# HydrophoneGroup1FilterAndAmpCircuit.net
KiCad netlist of a schematic drawn in Altium Designer
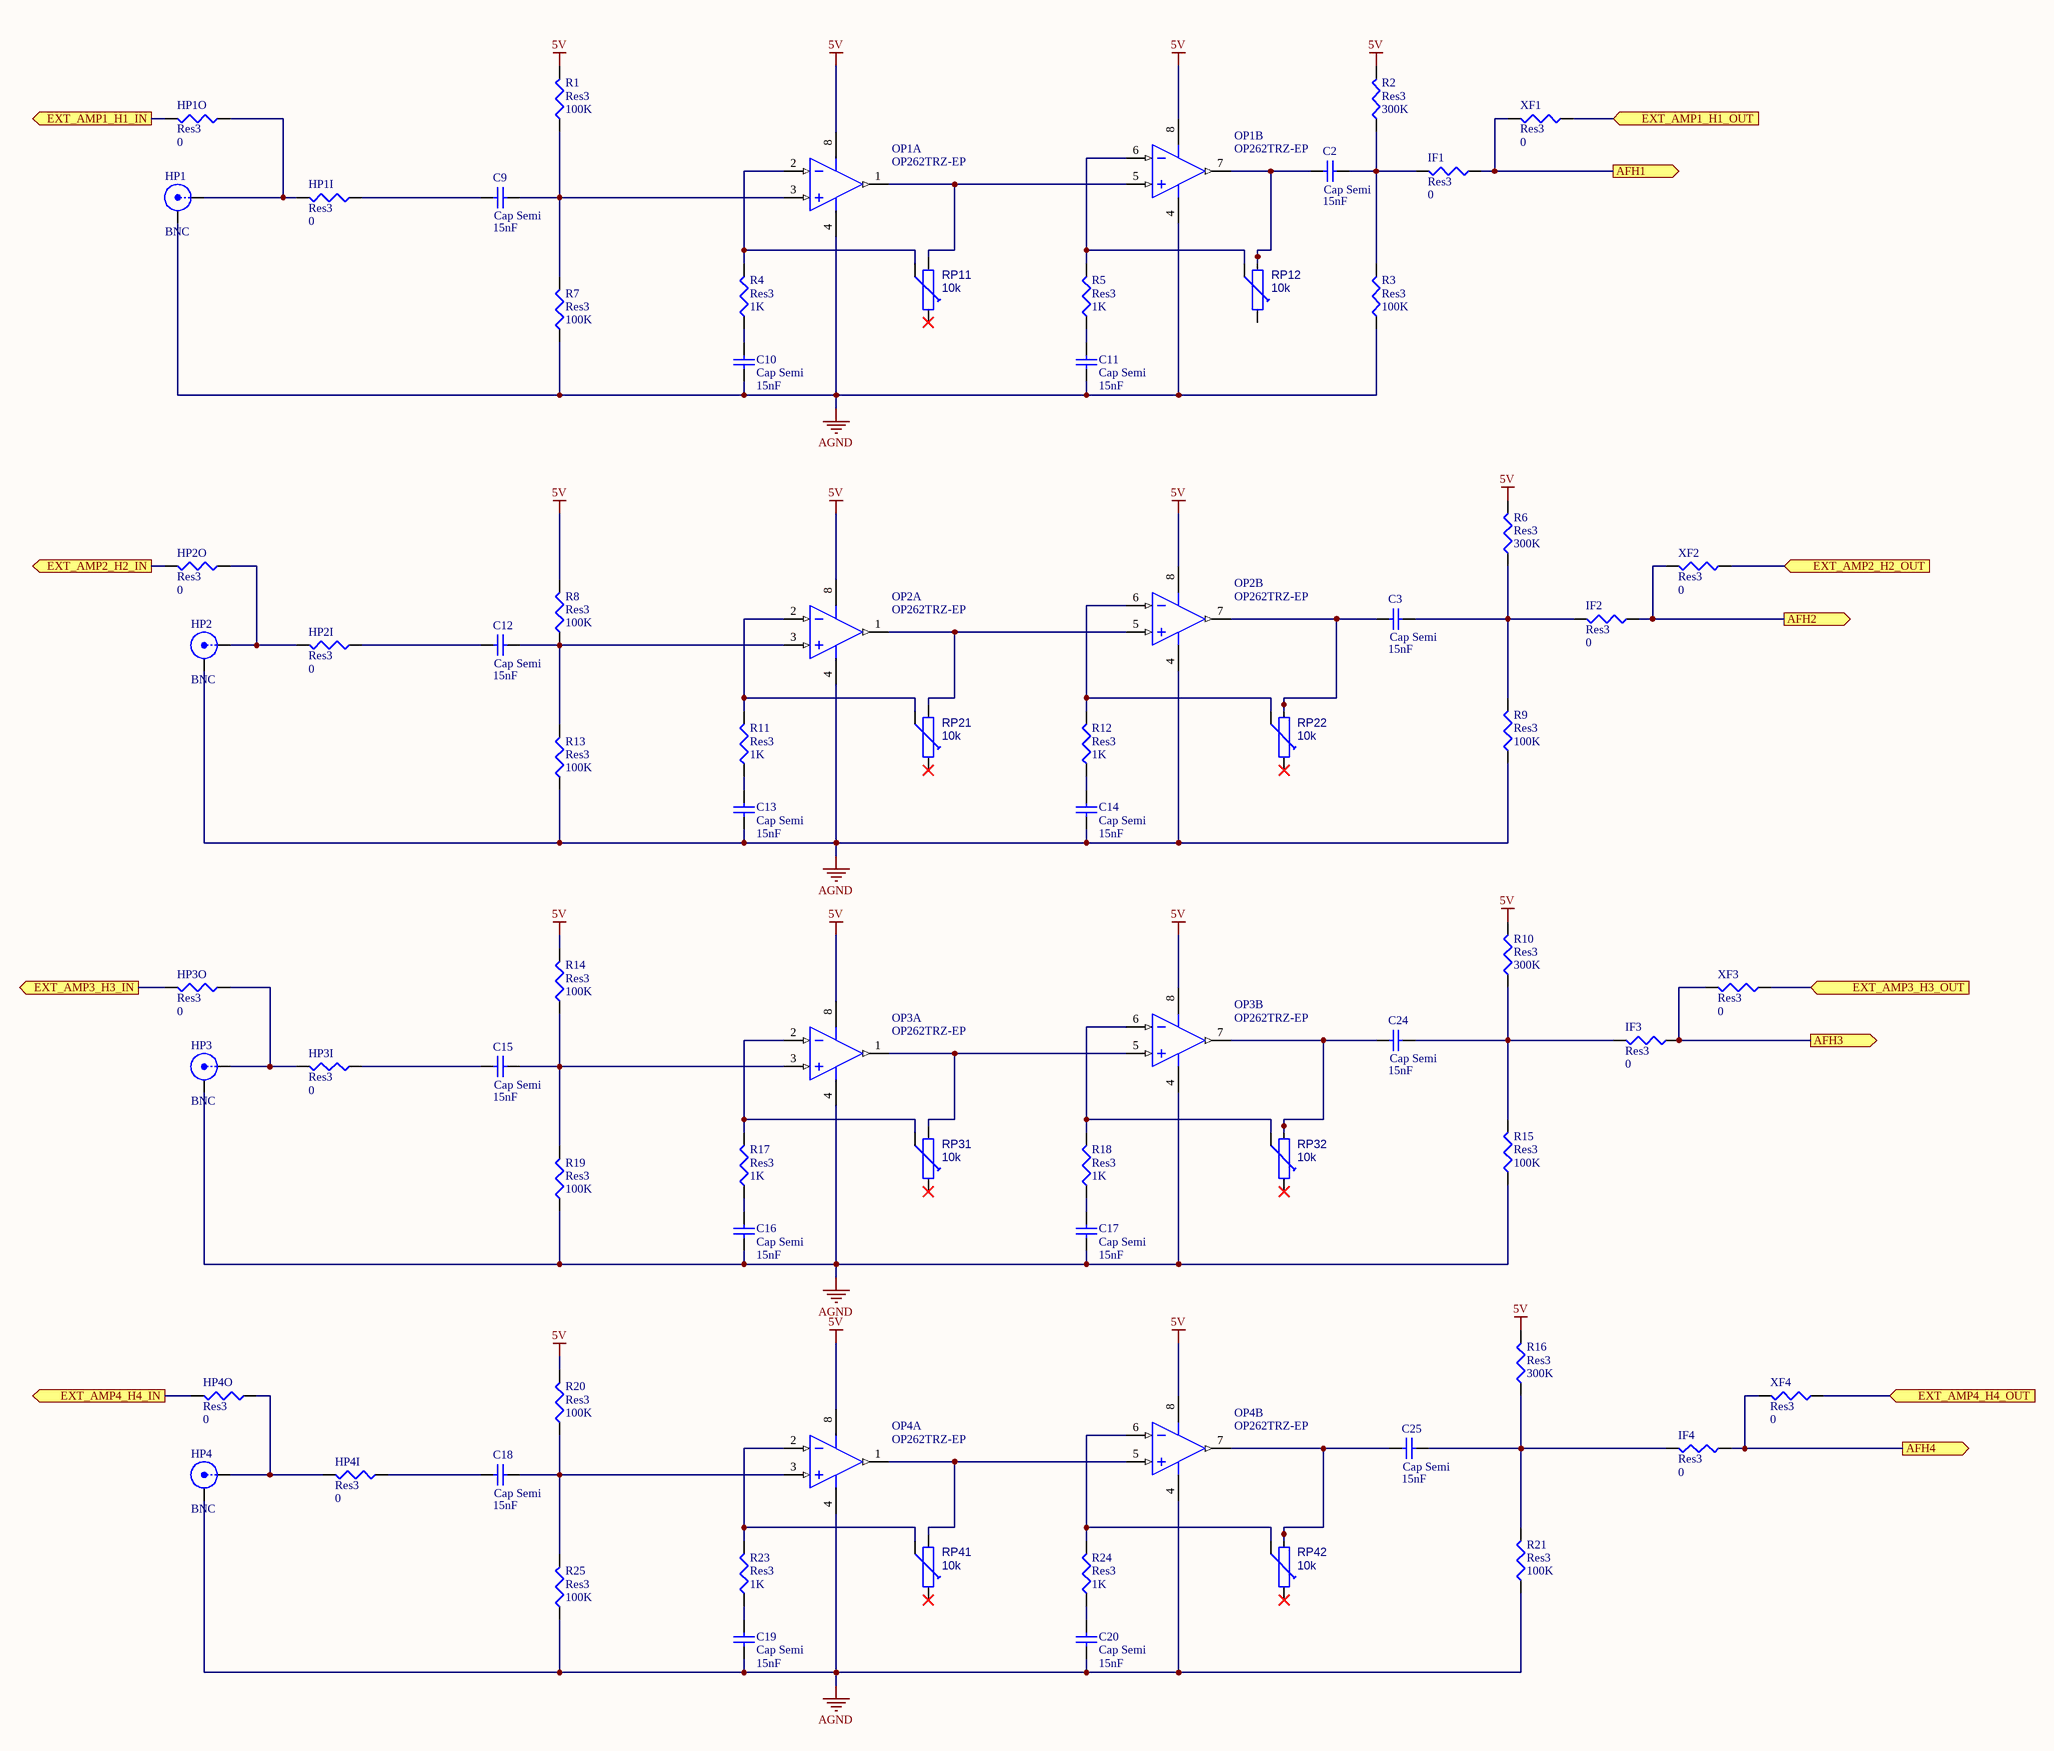
[diagram p0: HydrophoneGroup1FilterAndAmpCircuit.SchDoc]

(export (version "E")
  (design (tool "Eeschema 10.0.6"))
  (components
    (comp (ref "C2")
      (value "Cap Semi")
      (footprint "C0805")
      (description "Capacitor (Semiconductor SIM Model)")
      (fields (field (name "ALTIUM_VALUE") "15nF") (field (name "PUBLISHER") "Altium Limited"))
      (libsource (lib "Miscellaneous Devices") (part "Cap Semi"))
    )
    (comp (ref "C3")
      (value "Cap Semi")
      (footprint "C0805")
      (description "Capacitor (Semiconductor SIM Model)")
      (fields (field (name "ALTIUM_VALUE") "15nF") (field (name "PUBLISHER") "Altium Limited"))
      (libsource (lib "Miscellaneous Devices") (part "Cap Semi"))
    )
    (comp (ref "C9")
      (value "Cap Semi")
      (footprint "C0805")
      (description "Capacitor (Semiconductor SIM Model)")
      (fields (field (name "ALTIUM_VALUE") "15nF") (field (name "PUBLISHER") "Altium Limited"))
      (libsource (lib "Miscellaneous Devices") (part "Cap Semi"))
    )
    (comp (ref "C10")
      (value "Cap Semi")
      (footprint "C0805")
      (description "Capacitor (Semiconductor SIM Model)")
      (fields (field (name "ALTIUM_VALUE") "15nF") (field (name "PUBLISHER") "Altium Limited"))
      (libsource (lib "Miscellaneous Devices") (part "Cap Semi"))
    )
    (comp (ref "C11")
      (value "Cap Semi")
      (footprint "C0805")
      (description "Capacitor (Semiconductor SIM Model)")
      (fields (field (name "ALTIUM_VALUE") "15nF") (field (name "PUBLISHER") "Altium Limited"))
      (libsource (lib "Miscellaneous Devices") (part "Cap Semi"))
    )
    (comp (ref "C12")
      (value "Cap Semi")
      (footprint "C0805")
      (description "Capacitor (Semiconductor SIM Model)")
      (fields (field (name "ALTIUM_VALUE") "15nF") (field (name "PUBLISHER") "Altium Limited"))
      (libsource (lib "Miscellaneous Devices") (part "Cap Semi"))
    )
    (comp (ref "C13")
      (value "Cap Semi")
      (footprint "C0805")
      (description "Capacitor (Semiconductor SIM Model)")
      (fields (field (name "ALTIUM_VALUE") "15nF") (field (name "PUBLISHER") "Altium Limited"))
      (libsource (lib "Miscellaneous Devices") (part "Cap Semi"))
    )
    (comp (ref "C14")
      (value "Cap Semi")
      (footprint "C0805")
      (description "Capacitor (Semiconductor SIM Model)")
      (fields (field (name "ALTIUM_VALUE") "15nF") (field (name "PUBLISHER") "Altium Limited"))
      (libsource (lib "Miscellaneous Devices") (part "Cap Semi"))
    )
    (comp (ref "C15")
      (value "Cap Semi")
      (footprint "C0805")
      (description "Capacitor (Semiconductor SIM Model)")
      (fields (field (name "ALTIUM_VALUE") "15nF") (field (name "PUBLISHER") "Altium Limited"))
      (libsource (lib "Miscellaneous Devices") (part "Cap Semi"))
    )
    (comp (ref "C16")
      (value "Cap Semi")
      (footprint "C0805")
      (description "Capacitor (Semiconductor SIM Model)")
      (fields (field (name "ALTIUM_VALUE") "15nF") (field (name "PUBLISHER") "Altium Limited"))
      (libsource (lib "Miscellaneous Devices") (part "Cap Semi"))
    )
    (comp (ref "C17")
      (value "Cap Semi")
      (footprint "C0805")
      (description "Capacitor (Semiconductor SIM Model)")
      (fields (field (name "ALTIUM_VALUE") "15nF") (field (name "PUBLISHER") "Altium Limited"))
      (libsource (lib "Miscellaneous Devices") (part "Cap Semi"))
    )
    (comp (ref "C18")
      (value "Cap Semi")
      (footprint "C0805")
      (description "Capacitor (Semiconductor SIM Model)")
      (fields (field (name "ALTIUM_VALUE") "15nF") (field (name "PUBLISHER") "Altium Limited"))
      (libsource (lib "Miscellaneous Devices") (part "Cap Semi"))
    )
    (comp (ref "C19")
      (value "Cap Semi")
      (footprint "C0805")
      (description "Capacitor (Semiconductor SIM Model)")
      (fields (field (name "ALTIUM_VALUE") "15nF") (field (name "PUBLISHER") "Altium Limited"))
      (libsource (lib "Miscellaneous Devices") (part "Cap Semi"))
    )
    (comp (ref "C20")
      (value "Cap Semi")
      (footprint "C0805")
      (description "Capacitor (Semiconductor SIM Model)")
      (fields (field (name "ALTIUM_VALUE") "15nF") (field (name "PUBLISHER") "Altium Limited"))
      (libsource (lib "Miscellaneous Devices") (part "Cap Semi"))
    )
    (comp (ref "C24")
      (value "Cap Semi")
      (footprint "C0805")
      (description "Capacitor (Semiconductor SIM Model)")
      (fields (field (name "ALTIUM_VALUE") "15nF") (field (name "PUBLISHER") "Altium Limited"))
      (libsource (lib "Miscellaneous Devices") (part "Cap Semi"))
    )
    (comp (ref "C25")
      (value "Cap Semi")
      (footprint "C0805")
      (description "Capacitor (Semiconductor SIM Model)")
      (fields (field (name "ALTIUM_VALUE") "15nF") (field (name "PUBLISHER") "Altium Limited"))
      (libsource (lib "Miscellaneous Devices") (part "Cap Semi"))
    )
    (comp (ref "HP1")
      (value "BNC")
      (footprint "BNC_RA CON")
      (description "BNC Elbow Connector")
      (fields (field (name "PUBLISHER") "Altium Limited"))
      (libsource (lib "Miscellaneous Connectors") (part "BNC"))
    )
    (comp (ref "HP1I")
      (value "Res3")
      (footprint "J1-0603")
      (description "Resistor")
      (fields (field (name "ALTIUM_VALUE") "0") (field (name "PUBLISHER") "Altium Limited"))
      (libsource (lib "Miscellaneous Devices") (part "Res3"))
    )
    (comp (ref "HP1O")
      (value "Res3")
      (footprint "J1-0603")
      (description "Resistor")
      (fields (field (name "ALTIUM_VALUE") "0") (field (name "PUBLISHER") "Altium Limited"))
      (libsource (lib "Miscellaneous Devices") (part "Res3"))
    )
    (comp (ref "HP2")
      (value "BNC")
      (footprint "BNC_RA CON")
      (description "BNC Elbow Connector")
      (fields (field (name "PUBLISHER") "Altium Limited"))
      (libsource (lib "Miscellaneous Connectors") (part "BNC"))
    )
    (comp (ref "HP2I")
      (value "Res3")
      (footprint "J1-0603")
      (description "Resistor")
      (fields (field (name "ALTIUM_VALUE") "0") (field (name "PUBLISHER") "Altium Limited"))
      (libsource (lib "Miscellaneous Devices") (part "Res3"))
    )
    (comp (ref "HP2O")
      (value "Res3")
      (footprint "J1-0603")
      (description "Resistor")
      (fields (field (name "ALTIUM_VALUE") "0") (field (name "PUBLISHER") "Altium Limited"))
      (libsource (lib "Miscellaneous Devices") (part "Res3"))
    )
    (comp (ref "HP3")
      (value "BNC")
      (footprint "BNC_RA CON")
      (description "BNC Elbow Connector")
      (fields (field (name "PUBLISHER") "Altium Limited"))
      (libsource (lib "Miscellaneous Connectors") (part "BNC"))
    )
    (comp (ref "HP3I")
      (value "Res3")
      (footprint "J1-0603")
      (description "Resistor")
      (fields (field (name "ALTIUM_VALUE") "0") (field (name "PUBLISHER") "Altium Limited"))
      (libsource (lib "Miscellaneous Devices") (part "Res3"))
    )
    (comp (ref "HP3O")
      (value "Res3")
      (footprint "J1-0603")
      (description "Resistor")
      (fields (field (name "ALTIUM_VALUE") "0") (field (name "PUBLISHER") "Altium Limited"))
      (libsource (lib "Miscellaneous Devices") (part "Res3"))
    )
    (comp (ref "HP4")
      (value "BNC")
      (footprint "BNC_RA CON")
      (description "BNC Elbow Connector")
      (fields (field (name "PUBLISHER") "Altium Limited"))
      (libsource (lib "Miscellaneous Connectors") (part "BNC"))
    )
    (comp (ref "HP4I")
      (value "Res3")
      (footprint "J1-0603")
      (description "Resistor")
      (fields (field (name "ALTIUM_VALUE") "0") (field (name "PUBLISHER") "Altium Limited"))
      (libsource (lib "Miscellaneous Devices") (part "Res3"))
    )
    (comp (ref "HP4O")
      (value "Res3")
      (footprint "J1-0603")
      (description "Resistor")
      (fields (field (name "ALTIUM_VALUE") "0") (field (name "PUBLISHER") "Altium Limited"))
      (libsource (lib "Miscellaneous Devices") (part "Res3"))
    )
    (comp (ref "IF1")
      (value "Res3")
      (footprint "J1-0603")
      (description "Resistor")
      (fields (field (name "ALTIUM_VALUE") "0") (field (name "PUBLISHER") "Altium Limited"))
      (libsource (lib "Miscellaneous Devices") (part "Res3"))
    )
    (comp (ref "IF2")
      (value "Res3")
      (footprint "J1-0603")
      (description "Resistor")
      (fields (field (name "ALTIUM_VALUE") "0") (field (name "PUBLISHER") "Altium Limited"))
      (libsource (lib "Miscellaneous Devices") (part "Res3"))
    )
    (comp (ref "IF3")
      (value "Res3")
      (footprint "J1-0603")
      (description "Resistor")
      (fields (field (name "ALTIUM_VALUE") "0") (field (name "PUBLISHER") "Altium Limited"))
      (libsource (lib "Miscellaneous Devices") (part "Res3"))
    )
    (comp (ref "IF4")
      (value "Res3")
      (footprint "J1-0603")
      (description "Resistor")
      (fields (field (name "ALTIUM_VALUE") "0") (field (name "PUBLISHER") "Altium Limited"))
      (libsource (lib "Miscellaneous Devices") (part "Res3"))
    )
    (comp (ref "OP1")
      (value "OP262TRZ-EP")
      (footprint "ADI-R-8_N")
      (fields (field (name "GENERIC PART NUMBER") "OP262") (field (name "MANUFACTURER") "Analog Devices"))
      (libsource (lib "Analog Devices Operational Amplifiers") (part "OP262TRZ-EP"))
    )
    (comp (ref "OP2")
      (value "OP262TRZ-EP")
      (footprint "ADI-R-8_N")
      (fields (field (name "GENERIC PART NUMBER") "OP262") (field (name "MANUFACTURER") "Analog Devices"))
      (libsource (lib "Analog Devices Operational Amplifiers") (part "OP262TRZ-EP"))
    )
    (comp (ref "OP3")
      (value "OP262TRZ-EP")
      (footprint "ADI-R-8_N")
      (fields (field (name "GENERIC PART NUMBER") "OP262") (field (name "MANUFACTURER") "Analog Devices"))
      (libsource (lib "Analog Devices Operational Amplifiers") (part "OP262TRZ-EP"))
    )
    (comp (ref "OP4")
      (value "OP262TRZ-EP")
      (footprint "ADI-R-8_N")
      (fields (field (name "GENERIC PART NUMBER") "OP262") (field (name "MANUFACTURER") "Analog Devices"))
      (libsource (lib "Analog Devices Operational Amplifiers") (part "OP262TRZ-EP"))
    )
    (comp (ref "R1")
      (value "Res3")
      (footprint "J1-0603")
      (description "Resistor")
      (fields (field (name "ALTIUM_VALUE") "100K") (field (name "PUBLISHER") "Altium Limited"))
      (libsource (lib "Miscellaneous Devices") (part "Res3"))
    )
    (comp (ref "R2")
      (value "Res3")
      (footprint "J1-0603")
      (description "Resistor")
      (fields (field (name "ALTIUM_VALUE") "300K") (field (name "PUBLISHER") "Altium Limited"))
      (libsource (lib "Miscellaneous Devices") (part "Res3"))
    )
    (comp (ref "R3")
      (value "Res3")
      (footprint "J1-0603")
      (description "Resistor")
      (fields (field (name "ALTIUM_VALUE") "100K") (field (name "PUBLISHER") "Altium Limited"))
      (libsource (lib "Miscellaneous Devices") (part "Res3"))
    )
    (comp (ref "R4")
      (value "Res3")
      (footprint "J1-0603")
      (description "Resistor")
      (fields (field (name "ALTIUM_VALUE") "1K") (field (name "PUBLISHER") "Altium Limited"))
      (libsource (lib "Miscellaneous Devices") (part "Res3"))
    )
    (comp (ref "R5")
      (value "Res3")
      (footprint "J1-0603")
      (description "Resistor")
      (fields (field (name "ALTIUM_VALUE") "1K") (field (name "PUBLISHER") "Altium Limited"))
      (libsource (lib "Miscellaneous Devices") (part "Res3"))
    )
    (comp (ref "R6")
      (value "Res3")
      (footprint "J1-0603")
      (description "Resistor")
      (fields (field (name "ALTIUM_VALUE") "300K") (field (name "PUBLISHER") "Altium Limited"))
      (libsource (lib "Miscellaneous Devices") (part "Res3"))
    )
    (comp (ref "R7")
      (value "Res3")
      (footprint "J1-0603")
      (description "Resistor")
      (fields (field (name "ALTIUM_VALUE") "100K") (field (name "PUBLISHER") "Altium Limited"))
      (libsource (lib "Miscellaneous Devices") (part "Res3"))
    )
    (comp (ref "R8")
      (value "Res3")
      (footprint "J1-0603")
      (description "Resistor")
      (fields (field (name "ALTIUM_VALUE") "100K") (field (name "PUBLISHER") "Altium Limited"))
      (libsource (lib "Miscellaneous Devices") (part "Res3"))
    )
    (comp (ref "R9")
      (value "Res3")
      (footprint "J1-0603")
      (description "Resistor")
      (fields (field (name "ALTIUM_VALUE") "100K") (field (name "PUBLISHER") "Altium Limited"))
      (libsource (lib "Miscellaneous Devices") (part "Res3"))
    )
    (comp (ref "R10")
      (value "Res3")
      (footprint "J1-0603")
      (description "Resistor")
      (fields (field (name "ALTIUM_VALUE") "300K") (field (name "PUBLISHER") "Altium Limited"))
      (libsource (lib "Miscellaneous Devices") (part "Res3"))
    )
    (comp (ref "R11")
      (value "Res3")
      (footprint "J1-0603")
      (description "Resistor")
      (fields (field (name "ALTIUM_VALUE") "1K") (field (name "PUBLISHER") "Altium Limited"))
      (libsource (lib "Miscellaneous Devices") (part "Res3"))
    )
    (comp (ref "R12")
      (value "Res3")
      (footprint "J1-0603")
      (description "Resistor")
      (fields (field (name "ALTIUM_VALUE") "1K") (field (name "PUBLISHER") "Altium Limited"))
      (libsource (lib "Miscellaneous Devices") (part "Res3"))
    )
    (comp (ref "R13")
      (value "Res3")
      (footprint "J1-0603")
      (description "Resistor")
      (fields (field (name "ALTIUM_VALUE") "100K") (field (name "PUBLISHER") "Altium Limited"))
      (libsource (lib "Miscellaneous Devices") (part "Res3"))
    )
    (comp (ref "R14")
      (value "Res3")
      (footprint "J1-0603")
      (description "Resistor")
      (fields (field (name "ALTIUM_VALUE") "100K") (field (name "PUBLISHER") "Altium Limited"))
      (libsource (lib "Miscellaneous Devices") (part "Res3"))
    )
    (comp (ref "R15")
      (value "Res3")
      (footprint "J1-0603")
      (description "Resistor")
      (fields (field (name "ALTIUM_VALUE") "100K") (field (name "PUBLISHER") "Altium Limited"))
      (libsource (lib "Miscellaneous Devices") (part "Res3"))
    )
    (comp (ref "R16")
      (value "Res3")
      (footprint "J1-0603")
      (description "Resistor")
      (fields (field (name "ALTIUM_VALUE") "300K") (field (name "PUBLISHER") "Altium Limited"))
      (libsource (lib "Miscellaneous Devices") (part "Res3"))
    )
    (comp (ref "R17")
      (value "Res3")
      (footprint "J1-0603")
      (description "Resistor")
      (fields (field (name "ALTIUM_VALUE") "1K") (field (name "PUBLISHER") "Altium Limited"))
      (libsource (lib "Miscellaneous Devices") (part "Res3"))
    )
    (comp (ref "R18")
      (value "Res3")
      (footprint "J1-0603")
      (description "Resistor")
      (fields (field (name "ALTIUM_VALUE") "1K") (field (name "PUBLISHER") "Altium Limited"))
      (libsource (lib "Miscellaneous Devices") (part "Res3"))
    )
    (comp (ref "R19")
      (value "Res3")
      (footprint "J1-0603")
      (description "Resistor")
      (fields (field (name "ALTIUM_VALUE") "100K") (field (name "PUBLISHER") "Altium Limited"))
      (libsource (lib "Miscellaneous Devices") (part "Res3"))
    )
    (comp (ref "R20")
      (value "Res3")
      (footprint "J1-0603")
      (description "Resistor")
      (fields (field (name "ALTIUM_VALUE") "100K") (field (name "PUBLISHER") "Altium Limited"))
      (libsource (lib "Miscellaneous Devices") (part "Res3"))
    )
    (comp (ref "R21")
      (value "Res3")
      (footprint "J1-0603")
      (description "Resistor")
      (fields (field (name "ALTIUM_VALUE") "100K") (field (name "PUBLISHER") "Altium Limited"))
      (libsource (lib "Miscellaneous Devices") (part "Res3"))
    )
    (comp (ref "R23")
      (value "Res3")
      (footprint "J1-0603")
      (description "Resistor")
      (fields (field (name "ALTIUM_VALUE") "1K") (field (name "PUBLISHER") "Altium Limited"))
      (libsource (lib "Miscellaneous Devices") (part "Res3"))
    )
    (comp (ref "R24")
      (value "Res3")
      (footprint "J1-0603")
      (description "Resistor")
      (fields (field (name "ALTIUM_VALUE") "1K") (field (name "PUBLISHER") "Altium Limited"))
      (libsource (lib "Miscellaneous Devices") (part "Res3"))
    )
    (comp (ref "R25")
      (value "Res3")
      (footprint "J1-0603")
      (description "Resistor")
      (fields (field (name "ALTIUM_VALUE") "100K") (field (name "PUBLISHER") "Altium Limited"))
      (libsource (lib "Miscellaneous Devices") (part "Res3"))
    )
    (comp (ref "RP11")
      (value "10k")
      (footprint "Trim_Bourns3296")
      (description "Resistor Trimmer")
      (fields
        (field (name "PART_NUMBER") "RES_Trim_Bourns3296")
        (field (name "MFR PART NUMBER") "Bourns 3296Y-1-xxxLF")
      )
      (libsource (lib "Bourns") (part "RES_Trim"))
    )
    (comp (ref "RP12")
      (value "10k")
      (footprint "Trim_Bourns3296")
      (description "Resistor Trimmer")
      (fields
        (field (name "PART_NUMBER") "RES_Trim_Bourns3296")
        (field (name "MFR PART NUMBER") "Bourns 3296Y-1-xxxLF")
      )
      (libsource (lib "Bourns") (part "RES_Trim"))
    )
    (comp (ref "RP21")
      (value "10k")
      (footprint "Trim_Bourns3296")
      (description "Resistor Trimmer")
      (fields
        (field (name "PART_NUMBER") "RES_Trim_Bourns3296")
        (field (name "MFR PART NUMBER") "Bourns 3296Y-1-xxxLF")
      )
      (libsource (lib "Bourns") (part "RES_Trim"))
    )
    (comp (ref "RP22")
      (value "10k")
      (footprint "Trim_Bourns3296")
      (description "Resistor Trimmer")
      (fields
        (field (name "PART_NUMBER") "RES_Trim_Bourns3296")
        (field (name "MFR PART NUMBER") "Bourns 3296Y-1-xxxLF")
      )
      (libsource (lib "Bourns") (part "RES_Trim"))
    )
    (comp (ref "RP31")
      (value "10k")
      (footprint "Trim_Bourns3296")
      (description "Resistor Trimmer")
      (fields
        (field (name "PART_NUMBER") "RES_Trim_Bourns3296")
        (field (name "MFR PART NUMBER") "Bourns 3296Y-1-xxxLF")
      )
      (libsource (lib "Bourns") (part "RES_Trim"))
    )
    (comp (ref "RP32")
      (value "10k")
      (footprint "Trim_Bourns3296")
      (description "Resistor Trimmer")
      (fields
        (field (name "PART_NUMBER") "RES_Trim_Bourns3296")
        (field (name "MFR PART NUMBER") "Bourns 3296Y-1-xxxLF")
      )
      (libsource (lib "Bourns") (part "RES_Trim"))
    )
    (comp (ref "RP41")
      (value "10k")
      (footprint "Trim_Bourns3296")
      (description "Resistor Trimmer")
      (fields
        (field (name "PART_NUMBER") "RES_Trim_Bourns3296")
        (field (name "MFR PART NUMBER") "Bourns 3296Y-1-xxxLF")
      )
      (libsource (lib "Bourns") (part "RES_Trim"))
    )
    (comp (ref "RP42")
      (value "10k")
      (footprint "Trim_Bourns3296")
      (description "Resistor Trimmer")
      (fields
        (field (name "PART_NUMBER") "RES_Trim_Bourns3296")
        (field (name "MFR PART NUMBER") "Bourns 3296Y-1-xxxLF")
      )
      (libsource (lib "Bourns") (part "RES_Trim"))
    )
    (comp (ref "XF1")
      (value "Res3")
      (footprint "J1-0603")
      (description "Resistor")
      (fields (field (name "ALTIUM_VALUE") "0") (field (name "PUBLISHER") "Altium Limited"))
      (libsource (lib "Miscellaneous Devices") (part "Res3"))
    )
    (comp (ref "XF2")
      (value "Res3")
      (footprint "J1-0603")
      (description "Resistor")
      (fields (field (name "ALTIUM_VALUE") "0") (field (name "PUBLISHER") "Altium Limited"))
      (libsource (lib "Miscellaneous Devices") (part "Res3"))
    )
    (comp (ref "XF3")
      (value "Res3")
      (footprint "J1-0603")
      (description "Resistor")
      (fields (field (name "ALTIUM_VALUE") "0") (field (name "PUBLISHER") "Altium Limited"))
      (libsource (lib "Miscellaneous Devices") (part "Res3"))
    )
    (comp (ref "XF4")
      (value "Res3")
      (footprint "J1-0603")
      (description "Resistor")
      (fields (field (name "ALTIUM_VALUE") "0") (field (name "PUBLISHER") "Altium Limited"))
      (libsource (lib "Miscellaneous Devices") (part "Res3"))
    )
  )
  (nets
    (net (code "1") (name "/AFH1") (class "Default")
      (node (ref "IF1") (pin "1") (pinfunction "1_1") (pintype "passive"))
      (node (ref "XF1") (pin "2") (pinfunction "2_2") (pintype "passive"))
    )
    (net (code "2") (name "/AFH2") (class "Default")
      (node (ref "IF2") (pin "1") (pinfunction "1_1") (pintype "passive"))
      (node (ref "XF2") (pin "2") (pinfunction "2_2") (pintype "passive"))
    )
    (net (code "3") (name "/AFH3") (class "Default")
      (node (ref "IF3") (pin "1") (pinfunction "1_1") (pintype "passive"))
      (node (ref "XF3") (pin "2") (pinfunction "2_2") (pintype "passive"))
    )
    (net (code "4") (name "/AFH4") (class "Default")
      (node (ref "IF4") (pin "1") (pinfunction "1_1") (pintype "passive"))
      (node (ref "XF4") (pin "2") (pinfunction "2_2") (pintype "passive"))
    )
    (net (code "5") (name "/EXT_AMP1_H1_IN") (class "Default")
      (node (ref "HP1O") (pin "2") (pinfunction "2_2") (pintype "passive"))
    )
    (net (code "6") (name "/EXT_AMP1_H1_OUT") (class "Default")
      (node (ref "XF1") (pin "1") (pinfunction "1_1") (pintype "passive"))
    )
    (net (code "7") (name "/EXT_AMP2_H2_IN") (class "Default")
      (node (ref "HP2O") (pin "2") (pinfunction "2_2") (pintype "passive"))
    )
    (net (code "8") (name "/EXT_AMP2_H2_OUT") (class "Default")
      (node (ref "XF2") (pin "1") (pinfunction "1_1") (pintype "passive"))
    )
    (net (code "9") (name "/EXT_AMP3_H3_IN") (class "Default")
      (node (ref "HP3O") (pin "2") (pinfunction "2_2") (pintype "passive"))
    )
    (net (code "10") (name "/EXT_AMP3_H3_OUT") (class "Default")
      (node (ref "XF3") (pin "1") (pinfunction "1_1") (pintype "passive"))
    )
    (net (code "11") (name "/EXT_AMP4_H4_IN") (class "Default")
      (node (ref "HP4O") (pin "2") (pinfunction "2_2") (pintype "passive"))
    )
    (net (code "12") (name "/EXT_AMP4_H4_OUT") (class "Default")
      (node (ref "XF4") (pin "1") (pinfunction "1_1") (pintype "passive"))
    )
    (net (code "13") (name "5V") (class "Default")
      (node (ref "OP1") (pin "8") (pinfunction "+V_8") (pintype "power_in"))
      (node (ref "OP2") (pin "8") (pinfunction "+V_8") (pintype "power_in"))
      (node (ref "OP3") (pin "8") (pinfunction "+V_8") (pintype "power_in"))
      (node (ref "OP4") (pin "8") (pinfunction "+V_8") (pintype "power_in"))
      (node (ref "R1") (pin "2") (pinfunction "2_2") (pintype "passive"))
      (node (ref "R10") (pin "2") (pinfunction "2_2") (pintype "passive"))
      (node (ref "R14") (pin "2") (pinfunction "2_2") (pintype "passive"))
      (node (ref "R16") (pin "2") (pinfunction "2_2") (pintype "passive"))
      (node (ref "R2") (pin "2") (pinfunction "2_2") (pintype "passive"))
      (node (ref "R20") (pin "2") (pinfunction "2_2") (pintype "passive"))
      (node (ref "R6") (pin "2") (pinfunction "2_2") (pintype "passive"))
      (node (ref "R8") (pin "2") (pinfunction "2_2") (pintype "passive"))
    )
    (net (code "14") (name "AGND") (class "Default")
      (node (ref "C10") (pin "1") (pinfunction "1_1") (pintype "passive"))
      (node (ref "C11") (pin "1") (pinfunction "1_1") (pintype "passive"))
      (node (ref "C13") (pin "1") (pinfunction "1_1") (pintype "passive"))
      (node (ref "C14") (pin "1") (pinfunction "1_1") (pintype "passive"))
      (node (ref "C16") (pin "1") (pinfunction "1_1") (pintype "passive"))
      (node (ref "C17") (pin "1") (pinfunction "1_1") (pintype "passive"))
      (node (ref "C19") (pin "1") (pinfunction "1_1") (pintype "passive"))
      (node (ref "C20") (pin "1") (pinfunction "1_1") (pintype "passive"))
      (node (ref "HP1") (pin "2") (pinfunction "Y_2") (pintype "passive"))
      (node (ref "HP2") (pin "2") (pinfunction "Y_2") (pintype "passive"))
      (node (ref "HP3") (pin "2") (pinfunction "Y_2") (pintype "passive"))
      (node (ref "HP4") (pin "2") (pinfunction "Y_2") (pintype "passive"))
      (node (ref "OP1") (pin "4") (pinfunction "-V_4") (pintype "power_in"))
      (node (ref "OP2") (pin "4") (pinfunction "-V_4") (pintype "power_in"))
      (node (ref "OP3") (pin "4") (pinfunction "-V_4") (pintype "power_in"))
      (node (ref "OP4") (pin "4") (pinfunction "-V_4") (pintype "power_in"))
      (node (ref "R13") (pin "1") (pinfunction "1_1") (pintype "passive"))
      (node (ref "R15") (pin "1") (pinfunction "1_1") (pintype "passive"))
      (node (ref "R19") (pin "1") (pinfunction "1_1") (pintype "passive"))
      (node (ref "R21") (pin "1") (pinfunction "1_1") (pintype "passive"))
      (node (ref "R25") (pin "1") (pinfunction "1_1") (pintype "passive"))
      (node (ref "R3") (pin "1") (pinfunction "1_1") (pintype "passive"))
      (node (ref "R7") (pin "1") (pinfunction "1_1") (pintype "passive"))
      (node (ref "R9") (pin "1") (pinfunction "1_1") (pintype "passive"))
    )
    (net (code "15") (name "Net-(C2-Pad2)") (class "Default")
      (node (ref "C2") (pin "2") (pinfunction "2_2") (pintype "passive"))
      (node (ref "IF1") (pin "2") (pinfunction "2_2") (pintype "passive"))
      (node (ref "R2") (pin "1") (pinfunction "1_1") (pintype "passive"))
      (node (ref "R3") (pin "2") (pinfunction "2_2") (pintype "passive"))
    )
    (net (code "16") (name "Net-(C3-Pad2)") (class "Default")
      (node (ref "C3") (pin "2") (pinfunction "2_2") (pintype "passive"))
      (node (ref "IF2") (pin "2") (pinfunction "2_2") (pintype "passive"))
      (node (ref "R6") (pin "1") (pinfunction "1_1") (pintype "passive"))
      (node (ref "R9") (pin "2") (pinfunction "2_2") (pintype "passive"))
    )
    (net (code "17") (name "Net-(C9-Pad1)") (class "Default")
      (node (ref "C9") (pin "1") (pinfunction "1_1") (pintype "passive"))
      (node (ref "HP1I") (pin "1") (pinfunction "1_1") (pintype "passive"))
    )
    (net (code "18") (name "Net-(C10-Pad2)") (class "Default")
      (node (ref "C10") (pin "2") (pinfunction "2_2") (pintype "passive"))
      (node (ref "R4") (pin "1") (pinfunction "1_1") (pintype "passive"))
    )
    (net (code "19") (name "Net-(C11-Pad2)") (class "Default")
      (node (ref "C11") (pin "2") (pinfunction "2_2") (pintype "passive"))
      (node (ref "R5") (pin "1") (pinfunction "1_1") (pintype "passive"))
    )
    (net (code "20") (name "Net-(C12-Pad1)") (class "Default")
      (node (ref "C12") (pin "1") (pinfunction "1_1") (pintype "passive"))
      (node (ref "HP2I") (pin "1") (pinfunction "1_1") (pintype "passive"))
    )
    (net (code "21") (name "Net-(C13-Pad2)") (class "Default")
      (node (ref "C13") (pin "2") (pinfunction "2_2") (pintype "passive"))
      (node (ref "R11") (pin "1") (pinfunction "1_1") (pintype "passive"))
    )
    (net (code "22") (name "Net-(C14-Pad2)") (class "Default")
      (node (ref "C14") (pin "2") (pinfunction "2_2") (pintype "passive"))
      (node (ref "R12") (pin "1") (pinfunction "1_1") (pintype "passive"))
    )
    (net (code "23") (name "Net-(C15-Pad1)") (class "Default")
      (node (ref "C15") (pin "1") (pinfunction "1_1") (pintype "passive"))
      (node (ref "HP3I") (pin "1") (pinfunction "1_1") (pintype "passive"))
    )
    (net (code "24") (name "Net-(C16-Pad2)") (class "Default")
      (node (ref "C16") (pin "2") (pinfunction "2_2") (pintype "passive"))
      (node (ref "R17") (pin "1") (pinfunction "1_1") (pintype "passive"))
    )
    (net (code "25") (name "Net-(C17-Pad2)") (class "Default")
      (node (ref "C17") (pin "2") (pinfunction "2_2") (pintype "passive"))
      (node (ref "R18") (pin "1") (pinfunction "1_1") (pintype "passive"))
    )
    (net (code "26") (name "Net-(C18-Pad1)") (class "Default")
      (node (ref "C18") (pin "1") (pinfunction "1_1") (pintype "passive"))
      (node (ref "HP4I") (pin "1") (pinfunction "1_1") (pintype "passive"))
    )
    (net (code "27") (name "Net-(C19-Pad2)") (class "Default")
      (node (ref "C19") (pin "2") (pinfunction "2_2") (pintype "passive"))
      (node (ref "R23") (pin "1") (pinfunction "1_1") (pintype "passive"))
    )
    (net (code "28") (name "Net-(C20-Pad2)") (class "Default")
      (node (ref "C20") (pin "2") (pinfunction "2_2") (pintype "passive"))
      (node (ref "R24") (pin "1") (pinfunction "1_1") (pintype "passive"))
    )
    (net (code "29") (name "Net-(C24-Pad2)") (class "Default")
      (node (ref "C24") (pin "2") (pinfunction "2_2") (pintype "passive"))
      (node (ref "IF3") (pin "2") (pinfunction "2_2") (pintype "passive"))
      (node (ref "R10") (pin "1") (pinfunction "1_1") (pintype "passive"))
      (node (ref "R15") (pin "2") (pinfunction "2_2") (pintype "passive"))
    )
    (net (code "30") (name "Net-(C25-Pad2)") (class "Default")
      (node (ref "C25") (pin "2") (pinfunction "2_2") (pintype "passive"))
      (node (ref "IF4") (pin "2") (pinfunction "2_2") (pintype "passive"))
      (node (ref "R16") (pin "1") (pinfunction "1_1") (pintype "passive"))
      (node (ref "R21") (pin "2") (pinfunction "2_2") (pintype "passive"))
    )
    (net (code "31") (name "Net-(HP1-X)") (class "Default")
      (node (ref "HP1") (pin "1") (pinfunction "X_1") (pintype "passive"))
      (node (ref "HP1I") (pin "2") (pinfunction "2_2") (pintype "passive"))
      (node (ref "HP1O") (pin "1") (pinfunction "1_1") (pintype "passive"))
    )
    (net (code "32") (name "Net-(HP2-X)") (class "Default")
      (node (ref "HP2") (pin "1") (pinfunction "X_1") (pintype "passive"))
      (node (ref "HP2I") (pin "2") (pinfunction "2_2") (pintype "passive"))
      (node (ref "HP2O") (pin "1") (pinfunction "1_1") (pintype "passive"))
    )
    (net (code "33") (name "Net-(HP3-X)") (class "Default")
      (node (ref "HP3") (pin "1") (pinfunction "X_1") (pintype "passive"))
      (node (ref "HP3I") (pin "2") (pinfunction "2_2") (pintype "passive"))
      (node (ref "HP3O") (pin "1") (pinfunction "1_1") (pintype "passive"))
    )
    (net (code "34") (name "Net-(HP4-X)") (class "Default")
      (node (ref "HP4") (pin "1") (pinfunction "X_1") (pintype "passive"))
      (node (ref "HP4I") (pin "2") (pinfunction "2_2") (pintype "passive"))
      (node (ref "HP4O") (pin "1") (pinfunction "1_1") (pintype "passive"))
    )
    (net (code "35") (name "Net-(OP1A-+IN_A)") (class "Default")
      (node (ref "C9") (pin "2") (pinfunction "2_2") (pintype "passive"))
      (node (ref "OP1") (pin "3") (pinfunction "+IN_A_3") (pintype "input"))
      (node (ref "R1") (pin "1") (pinfunction "1_1") (pintype "passive"))
      (node (ref "R7") (pin "2") (pinfunction "2_2") (pintype "passive"))
    )
    (net (code "36") (name "Net-(OP1A--IN_A)") (class "Default")
      (node (ref "OP1") (pin "2") (pinfunction "-IN_A_2") (pintype "input"))
      (node (ref "R4") (pin "2") (pinfunction "2_2") (pintype "passive"))
      (node (ref "RP11") (pin "2") (pinfunction "2_2") (pintype "passive"))
    )
    (net (code "37") (name "Net-(OP1A-OUT_A)") (class "Default")
      (node (ref "OP1") (pin "1") (pinfunction "OUT_A_1") (pintype "output"))
      (node (ref "OP1") (pin "5") (pinfunction "+IN_B_5") (pintype "input"))
      (node (ref "RP11") (pin "1") (pinfunction "1_1") (pintype "passive"))
    )
    (net (code "38") (name "Net-(OP1B--IN_B)") (class "Default")
      (node (ref "OP1") (pin "6") (pinfunction "-IN_B_6") (pintype "input"))
      (node (ref "R5") (pin "2") (pinfunction "2_2") (pintype "passive"))
      (node (ref "RP12") (pin "2") (pinfunction "2_2") (pintype "passive"))
    )
    (net (code "39") (name "Net-(OP1B-OUT_B)") (class "Default")
      (node (ref "C2") (pin "1") (pinfunction "1_1") (pintype "passive"))
      (node (ref "OP1") (pin "7") (pinfunction "OUT_B_7") (pintype "output"))
      (node (ref "RP12") (pin "1") (pinfunction "1_1") (pintype "passive"))
    )
    (net (code "40") (name "Net-(OP2A-+IN_A)") (class "Default")
      (node (ref "C12") (pin "2") (pinfunction "2_2") (pintype "passive"))
      (node (ref "OP2") (pin "3") (pinfunction "+IN_A_3") (pintype "input"))
      (node (ref "R13") (pin "2") (pinfunction "2_2") (pintype "passive"))
      (node (ref "R8") (pin "1") (pinfunction "1_1") (pintype "passive"))
    )
    (net (code "41") (name "Net-(OP2A--IN_A)") (class "Default")
      (node (ref "OP2") (pin "2") (pinfunction "-IN_A_2") (pintype "input"))
      (node (ref "R11") (pin "2") (pinfunction "2_2") (pintype "passive"))
      (node (ref "RP21") (pin "2") (pinfunction "2_2") (pintype "passive"))
    )
    (net (code "42") (name "Net-(OP2A-OUT_A)") (class "Default")
      (node (ref "OP2") (pin "1") (pinfunction "OUT_A_1") (pintype "output"))
      (node (ref "OP2") (pin "5") (pinfunction "+IN_B_5") (pintype "input"))
      (node (ref "RP21") (pin "1") (pinfunction "1_1") (pintype "passive"))
    )
    (net (code "43") (name "Net-(OP2B--IN_B)") (class "Default")
      (node (ref "OP2") (pin "6") (pinfunction "-IN_B_6") (pintype "input"))
      (node (ref "R12") (pin "2") (pinfunction "2_2") (pintype "passive"))
      (node (ref "RP22") (pin "2") (pinfunction "2_2") (pintype "passive"))
    )
    (net (code "44") (name "Net-(OP2B-OUT_B)") (class "Default")
      (node (ref "C3") (pin "1") (pinfunction "1_1") (pintype "passive"))
      (node (ref "OP2") (pin "7") (pinfunction "OUT_B_7") (pintype "output"))
      (node (ref "RP22") (pin "1") (pinfunction "1_1") (pintype "passive"))
    )
    (net (code "45") (name "Net-(OP3A-+IN_A)") (class "Default")
      (node (ref "C15") (pin "2") (pinfunction "2_2") (pintype "passive"))
      (node (ref "OP3") (pin "3") (pinfunction "+IN_A_3") (pintype "input"))
      (node (ref "R14") (pin "1") (pinfunction "1_1") (pintype "passive"))
      (node (ref "R19") (pin "2") (pinfunction "2_2") (pintype "passive"))
    )
    (net (code "46") (name "Net-(OP3A--IN_A)") (class "Default")
      (node (ref "OP3") (pin "2") (pinfunction "-IN_A_2") (pintype "input"))
      (node (ref "R17") (pin "2") (pinfunction "2_2") (pintype "passive"))
      (node (ref "RP31") (pin "2") (pinfunction "2_2") (pintype "passive"))
    )
    (net (code "47") (name "Net-(OP3A-OUT_A)") (class "Default")
      (node (ref "OP3") (pin "1") (pinfunction "OUT_A_1") (pintype "output"))
      (node (ref "OP3") (pin "5") (pinfunction "+IN_B_5") (pintype "input"))
      (node (ref "RP31") (pin "1") (pinfunction "1_1") (pintype "passive"))
    )
    (net (code "48") (name "Net-(OP3B--IN_B)") (class "Default")
      (node (ref "OP3") (pin "6") (pinfunction "-IN_B_6") (pintype "input"))
      (node (ref "R18") (pin "2") (pinfunction "2_2") (pintype "passive"))
      (node (ref "RP32") (pin "2") (pinfunction "2_2") (pintype "passive"))
    )
    (net (code "49") (name "Net-(OP3B-OUT_B)") (class "Default")
      (node (ref "C24") (pin "1") (pinfunction "1_1") (pintype "passive"))
      (node (ref "OP3") (pin "7") (pinfunction "OUT_B_7") (pintype "output"))
      (node (ref "RP32") (pin "1") (pinfunction "1_1") (pintype "passive"))
    )
    (net (code "50") (name "Net-(OP4A-+IN_A)") (class "Default")
      (node (ref "C18") (pin "2") (pinfunction "2_2") (pintype "passive"))
      (node (ref "OP4") (pin "3") (pinfunction "+IN_A_3") (pintype "input"))
      (node (ref "R20") (pin "1") (pinfunction "1_1") (pintype "passive"))
      (node (ref "R25") (pin "2") (pinfunction "2_2") (pintype "passive"))
    )
    (net (code "51") (name "Net-(OP4A--IN_A)") (class "Default")
      (node (ref "OP4") (pin "2") (pinfunction "-IN_A_2") (pintype "input"))
      (node (ref "R23") (pin "2") (pinfunction "2_2") (pintype "passive"))
      (node (ref "RP41") (pin "2") (pinfunction "2_2") (pintype "passive"))
    )
    (net (code "52") (name "Net-(OP4A-OUT_A)") (class "Default")
      (node (ref "OP4") (pin "1") (pinfunction "OUT_A_1") (pintype "output"))
      (node (ref "OP4") (pin "5") (pinfunction "+IN_B_5") (pintype "input"))
      (node (ref "RP41") (pin "1") (pinfunction "1_1") (pintype "passive"))
    )
    (net (code "53") (name "Net-(OP4B--IN_B)") (class "Default")
      (node (ref "OP4") (pin "6") (pinfunction "-IN_B_6") (pintype "input"))
      (node (ref "R24") (pin "2") (pinfunction "2_2") (pintype "passive"))
      (node (ref "RP42") (pin "2") (pinfunction "2_2") (pintype "passive"))
    )
    (net (code "54") (name "Net-(OP4B-OUT_B)") (class "Default")
      (node (ref "C25") (pin "1") (pinfunction "1_1") (pintype "passive"))
      (node (ref "OP4") (pin "7") (pinfunction "OUT_B_7") (pintype "output"))
      (node (ref "RP42") (pin "1") (pinfunction "1_1") (pintype "passive"))
    )
    (net (code "55") (name "unconnected-(RP11-Pad3)") (class "Default")
      (node (ref "RP11") (pin "3") (pinfunction "3_3") (pintype "passive+no_connect"))
    )
    (net (code "56") (name "unconnected-(RP12-Pad3)") (class "Default")
      (node (ref "RP12") (pin "3") (pinfunction "3_3") (pintype "passive"))
    )
    (net (code "57") (name "unconnected-(RP21-Pad3)") (class "Default")
      (node (ref "RP21") (pin "3") (pinfunction "3_3") (pintype "passive+no_connect"))
    )
    (net (code "58") (name "unconnected-(RP22-Pad3)") (class "Default")
      (node (ref "RP22") (pin "3") (pinfunction "3_3") (pintype "passive+no_connect"))
    )
    (net (code "59") (name "unconnected-(RP31-Pad3)") (class "Default")
      (node (ref "RP31") (pin "3") (pinfunction "3_3") (pintype "passive+no_connect"))
    )
    (net (code "60") (name "unconnected-(RP32-Pad3)") (class "Default")
      (node (ref "RP32") (pin "3") (pinfunction "3_3") (pintype "passive+no_connect"))
    )
    (net (code "61") (name "unconnected-(RP41-Pad3)") (class "Default")
      (node (ref "RP41") (pin "3") (pinfunction "3_3") (pintype "passive+no_connect"))
    )
    (net (code "62") (name "unconnected-(RP42-Pad3)") (class "Default")
      (node (ref "RP42") (pin "3") (pinfunction "3_3") (pintype "passive+no_connect"))
    )
  )
)
